# CAN_Schematic.net
KiCad netlist of a schematic drawn in Altium Designer
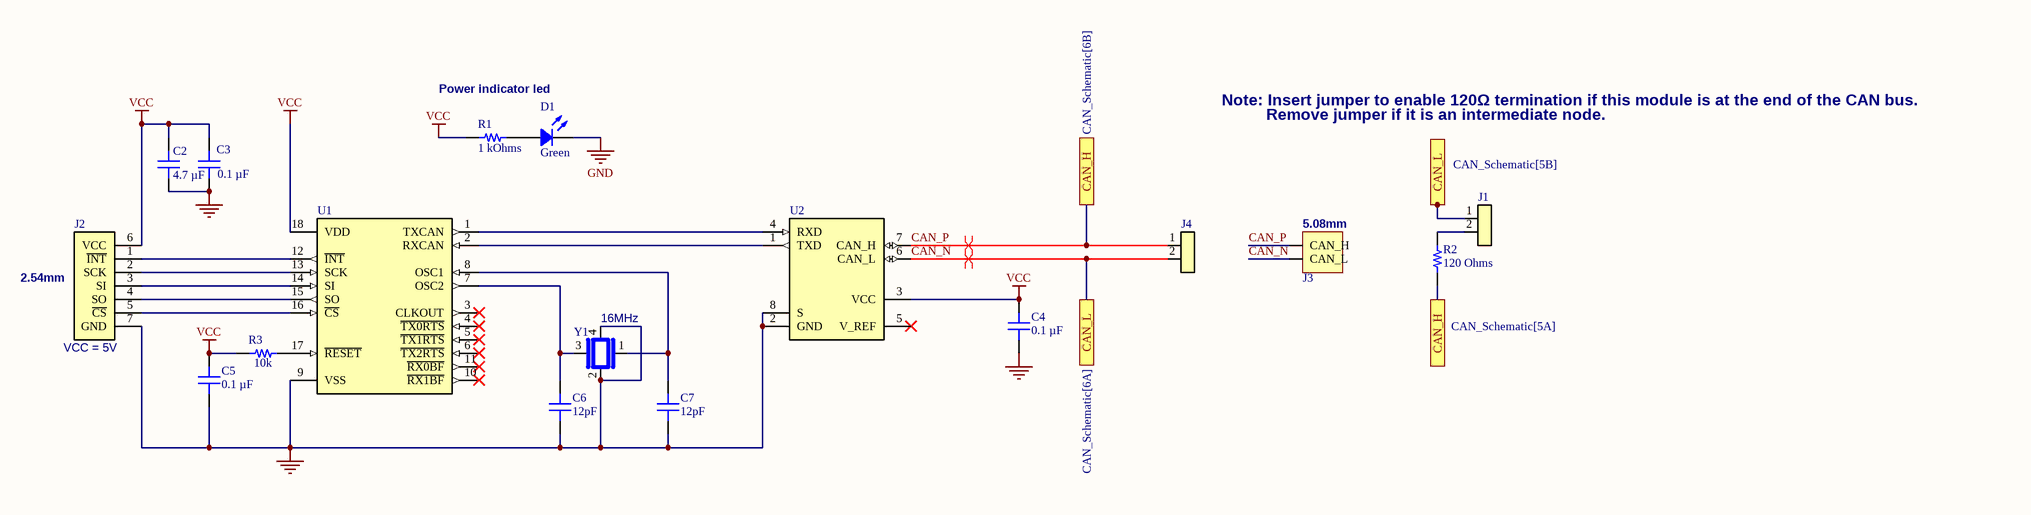
[diagram p0: CAN_Schematic.SchDoc]

(export (version "E")
  (design (tool "Eeschema 10.0.6"))
  (components
    (comp (ref "C2")
      (value "4.7 µF")
      (footprint "CAP 0603_1608")
      (description "CAP CER 4.7UF 16V X6S 0603")
      (fields
        (field (name "PART NUMBER") "0603YW475KAT2A")
        (field (name "CAPACITANCE") "4.7 µF")
        (field (name "MANUFACTURER") "KYOCERA AVX")
      )
      (libsource (lib "Celestial Altium Library - altium_library") (part "Capacitor"))
    )
    (comp (ref "C3")
      (value "0.1 µF")
      (footprint "CAP 0603_1608")
      (description "CAP CER 100NF 100V X8L 0603")
      (fields
        (field (name "PART NUMBER") "CL10E104KC8VPNC")
        (field (name "CAPACITANCE") "0.1 µF")
        (field (name "MANUFACTURER") "Samsung Electro-Mechanics")
      )
      (libsource (lib "Celestial Altium Library - altium_library") (part "Capacitor"))
    )
    (comp (ref "C4")
      (value "0.1 µF")
      (footprint "CAP 0603_1608")
      (description "CAP CER 100NF 100V X8L 0603")
      (fields
        (field (name "PART NUMBER") "CL10E104KC8VPNC")
        (field (name "CAPACITANCE") "0.1 µF")
        (field (name "MANUFACTURER") "Samsung Electro-Mechanics")
      )
      (libsource (lib "Celestial Altium Library - altium_library") (part "Capacitor"))
    )
    (comp (ref "C5")
      (value "0.1 µF")
      (footprint "CAP 0603_1608")
      (description "CAP CER 100NF 100V X8L 0603")
      (fields
        (field (name "PART NUMBER") "CL10E104KC8VPNC")
        (field (name "CAPACITANCE") "0.1 µF")
        (field (name "MANUFACTURER") "Samsung Electro-Mechanics")
      )
      (libsource (lib "Celestial Altium Library - altium_library") (part "Capacitor"))
    )
    (comp (ref "C6")
      (value "12pF")
      (footprint "CAP 0603_1608")
      (description "CAP CER 12PF 16V C0G/NP0 0603")
      (fields
        (field (name "PART NUMBER") "0603YA120KAT2A")
        (field (name "CAPACITANCE") "12pF")
        (field (name "MANUFACTURER") "AVX Corporation")
      )
      (libsource (lib "Celestial Altium Library - altium_library") (part "Capacitor"))
    )
    (comp (ref "C7")
      (value "12pF")
      (footprint "CAP 0603_1608")
      (description "CAP CER 12PF 16V C0G/NP0 0603")
      (fields
        (field (name "PART NUMBER") "0603YA120KAT2A")
        (field (name "CAPACITANCE") "12pF")
        (field (name "MANUFACTURER") "AVX Corporation")
      )
      (libsource (lib "Celestial Altium Library - altium_library") (part "Capacitor"))
    )
    (comp (ref "D1")
      (value "Green")
      (footprint "LED 0603_1608 GREEN")
      (description "LED GREEN 0603 SMD")
      (fields (field (name "PART NUMBER") "5973316507F") (field (name "MANUFACTURER") "Dialight"))
      (libsource (lib "Celestial Altium Library - altium_library") (part "LED"))
    )
    (comp (ref "J1")
      (value "PH1-02-UA")
      (footprint "CONN_PH1-02-UA_ADM")
      (description "No Description Available")
      (fields (field (name "COPYRIGHT") "Copyright (C) 2026 Ultra Librarian. All rights reserved."))
      (libsource (lib "CAN_SchematicLib") (part "PH1-02-UA"))
    )
    (comp (ref "J2")
      (value "CONN HEADER VERT 7POS 2.54MM")
      (footprint "CONN_PH1-07-UA_ADM")
      (fields
        (field (name "MANUFACTURER_PART_NUMBER") "PH1-07-UA")
        (field (name "COPYRIGHT") "Copyright (C) 2026 Ultra Librarian. All rights reserved.")
      )
      (libsource (lib "CAN_SchematicLib") (part "PH1-07-UA"))
    )
    (comp (ref "J3")
      (value "282837-2")
      (footprint "TE 282837-2")
      (description "TERM BLK 2P SIDE ENT 5.08MM PCB")
      (fields (field (name "MANUFACTURER") "TE Connectivity AMP Connectors") (field (name "VOLTAGE") "300 V"))
      (libsource (lib "Celestial Altium Library - altium_library") (part "2 Pin"))
    )
    (comp (ref "J4")
      (value "PH1-02-UA")
      (footprint "CONN_PH1-02-UA_ADM")
      (description "No Description Available")
      (fields (field (name "COPYRIGHT") "Copyright (C) 2026 Ultra Librarian. All rights reserved."))
      (libsource (lib "CAN_SchematicLib") (part "PH1-02-UA"))
    )
    (comp (ref "R1")
      (value "1 kOhms")
      (footprint "RES 0603_1608")
      (description "RES 1 KOHM 0.05% 1/10W 0603")
      (fields (field (name "PART NUMBER") "TNPU06031K00AYEA00") (field (name "MANUFACTURER") "Vishay Dale"))
      (libsource (lib "Celestial Altium Library - altium_library") (part "Resistor"))
    )
    (comp (ref "R2")
      (value "120 Ohms")
      (footprint "RES 0603_1608")
      (description "RES 120 OHM 0.05% 1/10W 0603")
      (fields (field (name "PART NUMBER") "TNPU0603120RAYEN00") (field (name "MANUFACTURER") "Vishay Dale"))
      (libsource (lib "Celestial Altium Library - altium_library") (part "Resistor"))
    )
    (comp (ref "R3")
      (value "10k")
      (footprint "RES 0603_1608")
      (description "RES 10K OHM 1% 1/10W 0603")
      (fields (field (name "PART NUMBER") "TNPW060310K0FHTA") (field (name "MANUFACTURER") "Vishay Dale"))
      (libsource (lib "Celestial Altium Library - altium_library") (part "Resistor"))
    )
    (comp (ref "U1")
      (value "CANbus Controller CAN 2.0 SPI Interface 18-SOIC")
      (footprint "SOIC18-1.27-11.5X7.5MM")
      (description "CAN controller w/ SPI interface18 SOIC .300in T/R ¦ Microchip Technology Inc. MCP2515T-I/SO")
      (fields (field (name "MF") "Microchip") (field (name "MP") "MCP2515T-I/SO"))
      (libsource (lib "CAN_SchematicLib") (part "MCP2515T-I/SO"))
    )
    (comp (ref "U2")
      (value "1/1 Transceiver Half CANbus 8-SO")
      (footprint "SOIC8")
      (description "TJA1050T Series 5.25 V 1 MBd Surface Mount High Speed CAN Transceiver - SOIC-8")
      (fields
        (field (name "MANUFACTURER") "NXP Semiconductors")
        (field (name "MANUFACTURER PART NUMBER") "TJA1050T/CM,118")
      )
      (libsource (lib "CAN_SchematicLib") (part "TJA1050T/CM,118"))
    )
    (comp (ref "Y1")
      (value "ABM8-16.000MHZ-10-1-U-T")
      (footprint "XTAL_ABM8-16.000MHZ-10-1-U-T")
      (description "16 MHz Â±10ppm Crystal 10pF 70 Ohms 4-SMD, No Lead")
      (fields (field (name "MF") "Abracon"))
      (libsource (lib "CAN_SchematicLib") (part "ABM8-16.000MHZ-10-1-U-T"))
    )
  )
  (nets
    (net (code "1") (name "/CAN_N") (class "Default")
      (node (ref "J1") (pin "1") (pinfunction "1_1") (pintype "passive"))
      (node (ref "J3") (pin "2") (pinfunction "CAN_L_2") (pintype "passive"))
      (node (ref "J4") (pin "2") (pinfunction "2_2") (pintype "passive"))
      (node (ref "U2") (pin "6") (pinfunction "CAN_L_6") (pintype "bidirectional"))
    )
    (net (code "2") (name "/CAN_P") (class "Default")
      (node (ref "J3") (pin "1") (pinfunction "CAN_H_1") (pintype "passive"))
      (node (ref "J4") (pin "1") (pinfunction "1_1") (pintype "passive"))
      (node (ref "R2") (pin "1") (pinfunction "1_1") (pintype "passive"))
      (node (ref "U2") (pin "7") (pinfunction "CAN_H_7") (pintype "bidirectional"))
    )
    (net (code "3") (name "GND") (class "Default")
      (node (ref "C2") (pin "1") (pinfunction "1_1") (pintype "passive"))
      (node (ref "C3") (pin "1") (pinfunction "1_1") (pintype "passive"))
      (node (ref "C4") (pin "1") (pinfunction "1_1") (pintype "passive"))
      (node (ref "C5") (pin "1") (pinfunction "1_1") (pintype "passive"))
      (node (ref "C6") (pin "1") (pinfunction "1_1") (pintype "passive"))
      (node (ref "C7") (pin "1") (pinfunction "1_1") (pintype "passive"))
      (node (ref "D1") (pin "2") (pinfunction "2_2") (pintype "passive"))
      (node (ref "J2") (pin "7") (pinfunction "GND_7") (pintype "passive"))
      (node (ref "U1") (pin "9") (pinfunction "VSS_9") (pintype "power_in"))
      (node (ref "U2") (pin "2") (pinfunction "GND_2") (pintype "power_in"))
      (node (ref "U2") (pin "8") (pinfunction "S_8") (pintype "passive"))
      (node (ref "Y1") (pin "2") (pinfunction "GND_2") (pintype "power_in"))
      (node (ref "Y1") (pin "4") (pinfunction "GND_4") (pintype "power_in"))
    )
    (net (code "4") (name "Net-(D1-Pad1)") (class "Default")
      (node (ref "D1") (pin "1") (pinfunction "1_1") (pintype "passive"))
      (node (ref "R1") (pin "2") (pinfunction "2_2") (pintype "passive"))
    )
    (net (code "5") (name "Net-(J1-Pad2)") (class "Default")
      (node (ref "J1") (pin "2") (pinfunction "2_2") (pintype "passive"))
      (node (ref "R2") (pin "2") (pinfunction "2_2") (pintype "passive"))
    )
    (net (code "6") (name "Net-(J2-SCK)") (class "Default")
      (node (ref "J2") (pin "2") (pinfunction "SCK_2") (pintype "passive"))
      (node (ref "U1") (pin "13") (pinfunction "SCK_13") (pintype "input"))
    )
    (net (code "7") (name "Net-(J2-SI)") (class "Default")
      (node (ref "J2") (pin "3") (pinfunction "SI_3") (pintype "passive"))
      (node (ref "U1") (pin "14") (pinfunction "SI_14") (pintype "input"))
    )
    (net (code "8") (name "Net-(J2-SO)") (class "Default")
      (node (ref "J2") (pin "4") (pinfunction "SO_4") (pintype "passive"))
      (node (ref "U1") (pin "15") (pinfunction "SO_15") (pintype "output"))
    )
    (net (code "9") (name "Net-(J2-~{CS})") (class "Default")
      (node (ref "J2") (pin "5") (pinfunction "~{CS}_5") (pintype "passive"))
      (node (ref "U1") (pin "16") (pinfunction "~{CS}_16") (pintype "input"))
    )
    (net (code "10") (name "Net-(J2-~{INT})") (class "Default")
      (node (ref "J2") (pin "1") (pinfunction "~{INT}_1") (pintype "passive"))
      (node (ref "U1") (pin "12") (pinfunction "~{INT}_12") (pintype "output"))
    )
    (net (code "11") (name "Net-(U1-OSC1)") (class "Default")
      (node (ref "C7") (pin "2") (pinfunction "2_2") (pintype "passive"))
      (node (ref "U1") (pin "8") (pinfunction "OSC1_8") (pintype "input"))
      (node (ref "Y1") (pin "1") (pinfunction "1_1") (pintype "passive"))
    )
    (net (code "12") (name "Net-(U1-OSC2)") (class "Default")
      (node (ref "C6") (pin "2") (pinfunction "2_2") (pintype "passive"))
      (node (ref "U1") (pin "7") (pinfunction "OSC2_7") (pintype "output"))
      (node (ref "Y1") (pin "3") (pinfunction "2_3") (pintype "passive"))
    )
    (net (code "13") (name "Net-(U1-RXCAN)") (class "Default")
      (node (ref "U1") (pin "2") (pinfunction "RXCAN_2") (pintype "input"))
      (node (ref "U2") (pin "1") (pinfunction "TXD_1") (pintype "output"))
    )
    (net (code "14") (name "Net-(U1-TXCAN)") (class "Default")
      (node (ref "U1") (pin "1") (pinfunction "TXCAN_1") (pintype "output"))
      (node (ref "U2") (pin "4") (pinfunction "RXD_4") (pintype "input"))
    )
    (net (code "15") (name "Net-(U1-~{RESET})") (class "Default")
      (node (ref "R3") (pin "2") (pinfunction "2_2") (pintype "passive"))
      (node (ref "U1") (pin "17") (pinfunction "~{RESET}_17") (pintype "input"))
    )
    (net (code "16") (name "VCC") (class "Default")
      (node (ref "C2") (pin "2") (pinfunction "2_2") (pintype "passive"))
      (node (ref "C3") (pin "2") (pinfunction "2_2") (pintype "passive"))
      (node (ref "C4") (pin "2") (pinfunction "2_2") (pintype "passive"))
      (node (ref "C5") (pin "2") (pinfunction "2_2") (pintype "passive"))
      (node (ref "J2") (pin "6") (pinfunction "VCC_6") (pintype "passive"))
      (node (ref "R1") (pin "1") (pinfunction "1_1") (pintype "passive"))
      (node (ref "R3") (pin "1") (pinfunction "1_1") (pintype "passive"))
      (node (ref "U1") (pin "18") (pinfunction "VDD_18") (pintype "power_in"))
      (node (ref "U2") (pin "3") (pinfunction "VCC_3") (pintype "power_in"))
    )
    (net (code "17") (name "unconnected-(U1-CLKOUT-Pad3)") (class "Default")
      (node (ref "U1") (pin "3") (pinfunction "CLKOUT_3") (pintype "output+no_connect"))
    )
    (net (code "18") (name "unconnected-(U1-~{RX0BF}-Pad11)") (class "Default")
      (node (ref "U1") (pin "11") (pinfunction "~{RX0BF}_11") (pintype "output+no_connect"))
    )
    (net (code "19") (name "unconnected-(U1-~{RX1BF}-Pad10)") (class "Default")
      (node (ref "U1") (pin "10") (pinfunction "~{RX1BF}_10") (pintype "output+no_connect"))
    )
    (net (code "20") (name "unconnected-(U1-~{TX0RTS}-Pad4)") (class "Default")
      (node (ref "U1") (pin "4") (pinfunction "~{TX0RTS}_4") (pintype "input+no_connect"))
    )
    (net (code "21") (name "unconnected-(U1-~{TX1RTS}-Pad5)") (class "Default")
      (node (ref "U1") (pin "5") (pinfunction "~{TX1RTS}_5") (pintype "input+no_connect"))
    )
    (net (code "22") (name "unconnected-(U1-~{TX2RTS}-Pad6)") (class "Default")
      (node (ref "U1") (pin "6") (pinfunction "~{TX2RTS}_6") (pintype "input+no_connect"))
    )
    (net (code "23") (name "unconnected-(U2-V_REF-Pad5)") (class "Default")
      (node (ref "U2") (pin "5") (pinfunction "V_REF_5") (pintype "power_in+no_connect"))
    )
  )
)
